# design.net
KiCad netlist of a schematic drawn in Altium Designer
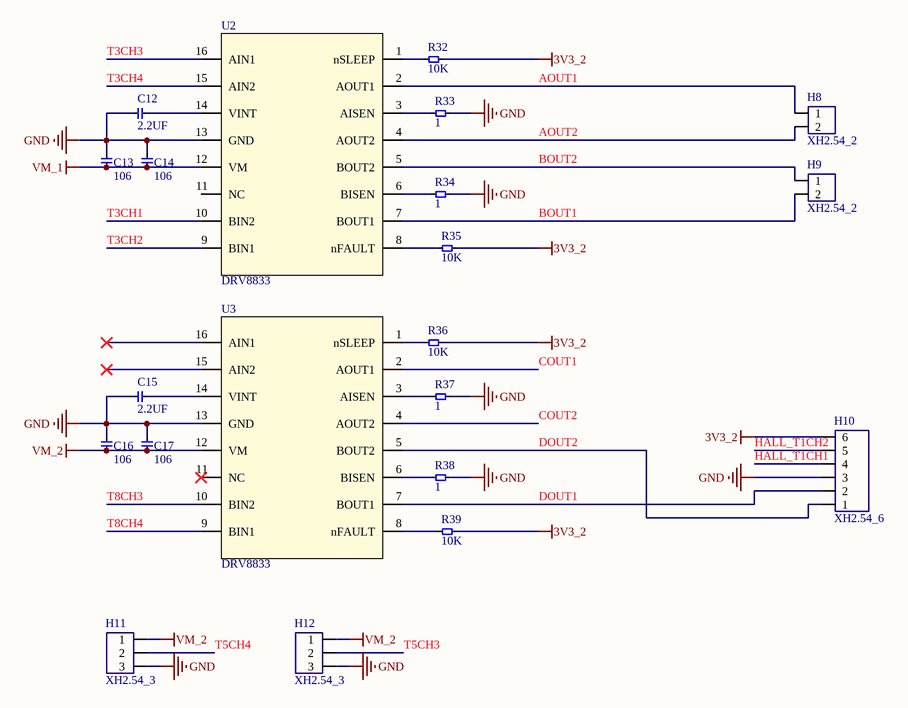
[diagram p0: 电机,舵机.SchDoc]

(export (version "E")
  (design (tool "Eeschema 10.0.6"))
  (components
    (comp (ref "C12")
      (value "2.2UF")
      (footprint "C_0603")
      (description "无极性贴片电容")
      (libsource (lib "电阻电容电感库") (part "C_无极贴片"))
    )
    (comp (ref "C13")
      (value "106")
      (footprint "C_0603")
      (description "无极性贴片电容")
      (libsource (lib "电阻电容电感库") (part "C_无极贴片"))
    )
    (comp (ref "C14")
      (value "106")
      (footprint "C_0603")
      (description "无极性贴片电容")
      (libsource (lib "电阻电容电感库") (part "C_无极贴片"))
    )
    (comp (ref "C15")
      (value "2.2UF")
      (footprint "C_0603")
      (description "无极性贴片电容")
      (libsource (lib "电阻电容电感库") (part "C_无极贴片"))
    )
    (comp (ref "C16")
      (value "106")
      (footprint "C_0603")
      (description "无极性贴片电容")
      (libsource (lib "电阻电容电感库") (part "C_无极贴片"))
    )
    (comp (ref "C17")
      (value "106")
      (footprint "C_0603")
      (description "无极性贴片电容")
      (libsource (lib "电阻电容电感库") (part "C_无极贴片"))
    )
    (comp (ref "H8")
      (value "XH2.54_2")
      (footprint "H_XH2.54_2")
      (description "2脚小白头")
      (fields (field (name "PUBLISHER") "Altium Limited"))
      (libsource (lib "接插件") (part "H_XH2.54_2"))
    )
    (comp (ref "H9")
      (value "XH2.54_2")
      (footprint "H_XH2.54_2")
      (description "2脚小白头")
      (fields (field (name "PUBLISHER") "Altium Limited"))
      (libsource (lib "接插件") (part "H_XH2.54_2"))
    )
    (comp (ref "H10")
      (value "XH2.54_6")
      (footprint "H_XH2.54_6")
      (description "6脚小白头")
      (fields (field (name "PUBLISHER") "Altium Limited"))
      (libsource (lib "接插件") (part "H_XH2.54_6"))
    )
    (comp (ref "H11")
      (value "XH2.54_3")
      (footprint "H_XH2.54_3")
      (description "3脚小白头")
      (fields (field (name "PUBLISHER") "Altium Limited"))
      (libsource (lib "接插件") (part "H_XH2.54_3"))
    )
    (comp (ref "H12")
      (value "XH2.54_3")
      (footprint "H_XH2.54_3")
      (description "3脚小白头")
      (fields (field (name "PUBLISHER") "Altium Limited"))
      (libsource (lib "接插件") (part "H_XH2.54_3"))
    )
    (comp (ref "R32")
      (value "10K")
      (footprint "R_0603")
      (description "贴片电阻")
      (libsource (lib "电阻电容电感库") (part "R_贴片"))
    )
    (comp (ref "R33")
      (value "1")
      (footprint "R_1206")
      (description "贴片电阻")
      (libsource (lib "电阻电容电感库") (part "R_贴片"))
    )
    (comp (ref "R34")
      (value "1")
      (footprint "R_1206")
      (description "贴片电阻")
      (libsource (lib "电阻电容电感库") (part "R_贴片"))
    )
    (comp (ref "R35")
      (value "10K")
      (footprint "R_0603")
      (description "贴片电阻")
      (libsource (lib "电阻电容电感库") (part "R_贴片"))
    )
    (comp (ref "R36")
      (value "10K")
      (footprint "R_0603")
      (description "贴片电阻")
      (libsource (lib "电阻电容电感库") (part "R_贴片"))
    )
    (comp (ref "R37")
      (value "1")
      (footprint "R_1206")
      (description "贴片电阻")
      (libsource (lib "电阻电容电感库") (part "R_贴片"))
    )
    (comp (ref "R38")
      (value "1")
      (footprint "R_1206")
      (description "贴片电阻")
      (libsource (lib "电阻电容电感库") (part "R_贴片"))
    )
    (comp (ref "R39")
      (value "10K")
      (footprint "R_0603")
      (description "贴片电阻")
      (libsource (lib "电阻电容电感库") (part "R_贴片"))
    )
    (comp (ref "U2") (value "DRV8833") (footprint "SSOP16") (libsource (lib "王建勇") (part "DRV8833")))
    (comp (ref "U3") (value "DRV8833") (footprint "SSOP16") (libsource (lib "王建勇") (part "DRV8833")))
  )
  (nets
    (net (code "1") (name "/AOUT1") (class "Default")
      (node (ref "H8") (pin "1") (pinfunction "1_1") (pintype "passive"))
      (node (ref "U2") (pin "2") (pinfunction "AOUT1_2") (pintype "passive"))
    )
    (net (code "2") (name "/AOUT2") (class "Default")
      (node (ref "H8") (pin "2") (pinfunction "2_2") (pintype "passive"))
      (node (ref "U2") (pin "4") (pinfunction "AOUT2_4") (pintype "passive"))
    )
    (net (code "3") (name "/BOUT1") (class "Default")
      (node (ref "H9") (pin "2") (pinfunction "2_2") (pintype "passive"))
      (node (ref "U2") (pin "7") (pinfunction "BOUT1_7") (pintype "passive"))
    )
    (net (code "4") (name "/BOUT2") (class "Default")
      (node (ref "H9") (pin "1") (pinfunction "1_1") (pintype "passive"))
      (node (ref "U2") (pin "5") (pinfunction "BOUT2_5") (pintype "passive"))
    )
    (net (code "5") (name "/COUT1") (class "Default")
      (node (ref "U3") (pin "2") (pinfunction "AOUT1_2") (pintype "passive"))
    )
    (net (code "6") (name "/COUT2") (class "Default")
      (node (ref "U3") (pin "4") (pinfunction "AOUT2_4") (pintype "passive"))
    )
    (net (code "7") (name "/DOUT1") (class "Default")
      (node (ref "H10") (pin "2") (pinfunction "2_2") (pintype "passive"))
      (node (ref "U3") (pin "7") (pinfunction "BOUT1_7") (pintype "passive"))
    )
    (net (code "8") (name "/DOUT2") (class "Default")
      (node (ref "H10") (pin "1") (pinfunction "1_1") (pintype "passive"))
      (node (ref "U3") (pin "5") (pinfunction "BOUT2_5") (pintype "passive"))
    )
    (net (code "9") (name "/HALL_T1CH1") (class "Default")
      (node (ref "H10") (pin "4") (pinfunction "4_4") (pintype "passive"))
    )
    (net (code "10") (name "/HALL_T1CH2") (class "Default")
      (node (ref "H10") (pin "5") (pinfunction "5_5") (pintype "passive"))
    )
    (net (code "11") (name "/T3CH1") (class "Default")
      (node (ref "U2") (pin "10") (pinfunction "BIN2_10") (pintype "passive"))
    )
    (net (code "12") (name "/T3CH2") (class "Default")
      (node (ref "U2") (pin "9") (pinfunction "BIN1_9") (pintype "passive"))
    )
    (net (code "13") (name "/T3CH3") (class "Default")
      (node (ref "U2") (pin "16") (pinfunction "AIN1_16") (pintype "passive"))
    )
    (net (code "14") (name "/T3CH4") (class "Default")
      (node (ref "U2") (pin "15") (pinfunction "AIN2_15") (pintype "passive"))
    )
    (net (code "15") (name "/T5CH3") (class "Default")
      (node (ref "H12") (pin "2") (pinfunction "2_2") (pintype "passive"))
    )
    (net (code "16") (name "/T5CH4") (class "Default")
      (node (ref "H11") (pin "2") (pinfunction "2_2") (pintype "passive"))
    )
    (net (code "17") (name "/T8CH3") (class "Default")
      (node (ref "U3") (pin "10") (pinfunction "BIN2_10") (pintype "passive"))
    )
    (net (code "18") (name "/T8CH4") (class "Default")
      (node (ref "U3") (pin "9") (pinfunction "BIN1_9") (pintype "passive"))
    )
    (net (code "19") (name "3V3_2") (class "Default")
      (node (ref "H10") (pin "6") (pinfunction "6_6") (pintype "passive"))
      (node (ref "R32") (pin "2") (pintype "passive"))
      (node (ref "R35") (pin "2") (pintype "passive"))
      (node (ref "R36") (pin "2") (pintype "passive"))
      (node (ref "R39") (pin "2") (pintype "passive"))
    )
    (net (code "20") (name "GND") (class "Default")
      (node (ref "C12") (pin "2") (pinfunction "2_2") (pintype "passive"))
      (node (ref "C13") (pin "2") (pinfunction "2_2") (pintype "passive"))
      (node (ref "C14") (pin "2") (pinfunction "2_2") (pintype "passive"))
      (node (ref "C15") (pin "2") (pinfunction "2_2") (pintype "passive"))
      (node (ref "C16") (pin "2") (pinfunction "2_2") (pintype "passive"))
      (node (ref "C17") (pin "2") (pinfunction "2_2") (pintype "passive"))
      (node (ref "H10") (pin "3") (pinfunction "3_3") (pintype "passive"))
      (node (ref "H11") (pin "3") (pinfunction "3_3") (pintype "passive"))
      (node (ref "H12") (pin "3") (pinfunction "3_3") (pintype "passive"))
      (node (ref "R33") (pin "2") (pintype "passive"))
      (node (ref "R34") (pin "2") (pintype "passive"))
      (node (ref "R37") (pin "2") (pintype "passive"))
      (node (ref "R38") (pin "2") (pintype "passive"))
      (node (ref "U2") (pin "13") (pinfunction "GND_13") (pintype "passive"))
      (node (ref "U3") (pin "13") (pinfunction "GND_13") (pintype "passive"))
    )
    (net (code "21") (name "Net-(U2-AISEN)") (class "Default")
      (node (ref "R33") (pin "1") (pintype "passive"))
      (node (ref "U2") (pin "3") (pinfunction "AISEN_3") (pintype "passive"))
    )
    (net (code "22") (name "Net-(U2-BISEN)") (class "Default")
      (node (ref "R34") (pin "1") (pintype "passive"))
      (node (ref "U2") (pin "6") (pinfunction "BISEN_6") (pintype "passive"))
    )
    (net (code "23") (name "Net-(U2-VINT)") (class "Default")
      (node (ref "C12") (pin "1") (pinfunction "1_1") (pintype "passive"))
      (node (ref "U2") (pin "14") (pinfunction "VINT_14") (pintype "passive"))
    )
    (net (code "24") (name "Net-(U2-nFAULT)") (class "Default")
      (node (ref "R35") (pin "1") (pintype "passive"))
      (node (ref "U2") (pin "8") (pinfunction "nFAULT_8") (pintype "passive"))
    )
    (net (code "25") (name "Net-(U2-nSLEEP)") (class "Default")
      (node (ref "R32") (pin "1") (pintype "passive"))
      (node (ref "U2") (pin "1") (pinfunction "nSLEEP_1") (pintype "passive"))
    )
    (net (code "26") (name "Net-(U3-AISEN)") (class "Default")
      (node (ref "R37") (pin "1") (pintype "passive"))
      (node (ref "U3") (pin "3") (pinfunction "AISEN_3") (pintype "passive"))
    )
    (net (code "27") (name "Net-(U3-BISEN)") (class "Default")
      (node (ref "R38") (pin "1") (pintype "passive"))
      (node (ref "U3") (pin "6") (pinfunction "BISEN_6") (pintype "passive"))
    )
    (net (code "28") (name "Net-(U3-VINT)") (class "Default")
      (node (ref "C15") (pin "1") (pinfunction "1_1") (pintype "passive"))
      (node (ref "U3") (pin "14") (pinfunction "VINT_14") (pintype "passive"))
    )
    (net (code "29") (name "Net-(U3-nFAULT)") (class "Default")
      (node (ref "R39") (pin "1") (pintype "passive"))
      (node (ref "U3") (pin "8") (pinfunction "nFAULT_8") (pintype "passive"))
    )
    (net (code "30") (name "Net-(U3-nSLEEP)") (class "Default")
      (node (ref "R36") (pin "1") (pintype "passive"))
      (node (ref "U3") (pin "1") (pinfunction "nSLEEP_1") (pintype "passive"))
    )
    (net (code "31") (name "VM_1") (class "Default")
      (node (ref "C13") (pin "1") (pinfunction "1_1") (pintype "passive"))
      (node (ref "C14") (pin "1") (pinfunction "1_1") (pintype "passive"))
      (node (ref "U2") (pin "12") (pinfunction "VM_12") (pintype "passive"))
    )
    (net (code "32") (name "VM_2") (class "Default")
      (node (ref "C16") (pin "1") (pinfunction "1_1") (pintype "passive"))
      (node (ref "C17") (pin "1") (pinfunction "1_1") (pintype "passive"))
      (node (ref "H11") (pin "1") (pinfunction "1_1") (pintype "passive"))
      (node (ref "H12") (pin "1") (pinfunction "1_1") (pintype "passive"))
      (node (ref "U3") (pin "12") (pinfunction "VM_12") (pintype "passive"))
    )
    (net (code "33") (name "unconnected-(U2-NC-Pad11)") (class "Default")
      (node (ref "U2") (pin "11") (pinfunction "NC_11") (pintype "passive"))
    )
    (net (code "34") (name "unconnected-(U3-AIN1-Pad16)") (class "Default")
      (node (ref "U3") (pin "16") (pinfunction "AIN1_16") (pintype "passive+no_connect"))
    )
    (net (code "35") (name "unconnected-(U3-AIN2-Pad15)") (class "Default")
      (node (ref "U3") (pin "15") (pinfunction "AIN2_15") (pintype "passive+no_connect"))
    )
    (net (code "36") (name "unconnected-(U3-NC-Pad11)") (class "Default")
      (node (ref "U3") (pin "11") (pinfunction "NC_11") (pintype "passive+no_connect"))
    )
  )
)
